# Main_backup1.net
KiCad netlist of a schematic drawn in EAGLE
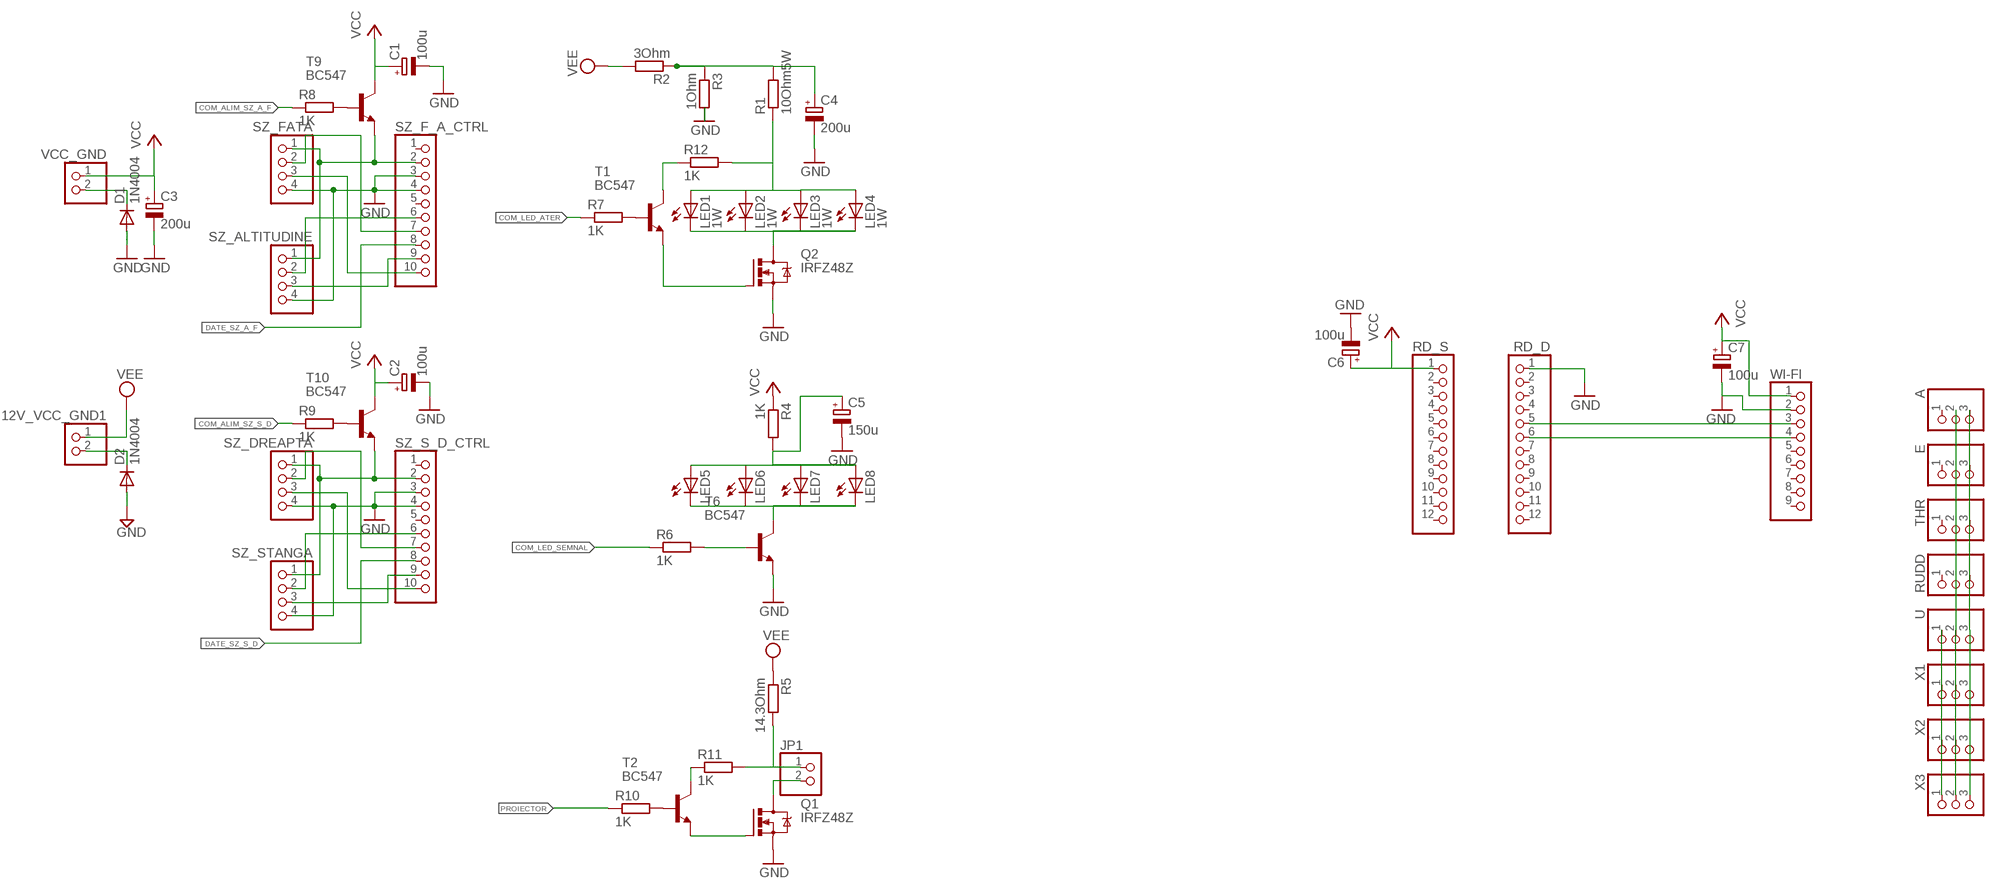
[diagram p0: schematic, sheet 1]

(export (version "E")
  (design (tool "Eeschema 10.0.6"))
  (components
    (comp (ref "12V_VCC_GND1")
      (value "PINHD-1X2")
      (footprint "eagle-import:1X02")
      (libsource (lib "eagle-import") (part "PINHD-1X2"))
    )
    (comp (ref "A")
      (value "PINHD-1X3/90")
      (footprint "eagle-import:1X03_90")
      (libsource (lib "eagle-import") (part "PINHD-1X3/90"))
    )
    (comp (ref "C1")
      (value "100u")
      (footprint "eagle-import:E2-5")
      (libsource (lib "eagle-import") (part "CPOL-EUE2-5"))
    )
    (comp (ref "C2")
      (value "100u")
      (footprint "eagle-import:E2-5")
      (libsource (lib "eagle-import") (part "CPOL-EUE2-5"))
    )
    (comp (ref "C3")
      (value "200u")
      (footprint "eagle-import:E2-5")
      (libsource (lib "eagle-import") (part "CPOL-EUE2-5"))
    )
    (comp (ref "C4")
      (value "200u")
      (footprint "eagle-import:E2-5")
      (libsource (lib "eagle-import") (part "CPOL-EUE2-5"))
    )
    (comp (ref "C5")
      (value "150u")
      (footprint "eagle-import:E2-5")
      (libsource (lib "eagle-import") (part "CPOL-EUE2-5"))
    )
    (comp (ref "C6")
      (value "100u")
      (footprint "eagle-import:E2-5")
      (libsource (lib "eagle-import") (part "CPOL-EUE2-5"))
    )
    (comp (ref "C7")
      (value "100u")
      (footprint "eagle-import:E2-5")
      (libsource (lib "eagle-import") (part "CPOL-EUE2-5"))
    )
    (comp (ref "D1")
      (value "1N4004")
      (footprint "eagle-import:DO41-10")
      (libsource (lib "eagle-import") (part "1N4004"))
    )
    (comp (ref "D2")
      (value "1N4004")
      (footprint "eagle-import:DO41-10")
      (libsource (lib "eagle-import") (part "1N4004"))
    )
    (comp (ref "E")
      (value "PINHD-1X3/90")
      (footprint "eagle-import:1X03_90")
      (libsource (lib "eagle-import") (part "PINHD-1X3/90"))
    )
    (comp (ref "JP1")
      (value "PINHD-1X2")
      (footprint "eagle-import:1X02")
      (libsource (lib "eagle-import") (part "PINHD-1X2"))
    )
    (comp (ref "LED1")
      (value "1W")
      (footprint "eagle-import:OSRAM-SIDELED")
      (libsource (lib "eagle-import") (part "LEDSIDELED"))
    )
    (comp (ref "LED2")
      (value "1W")
      (footprint "eagle-import:OSRAM-SIDELED")
      (libsource (lib "eagle-import") (part "LEDSIDELED"))
    )
    (comp (ref "LED3")
      (value "1W")
      (footprint "eagle-import:OSRAM-SIDELED")
      (libsource (lib "eagle-import") (part "LEDSIDELED"))
    )
    (comp (ref "LED4")
      (value "1W")
      (footprint "eagle-import:OSRAM-SIDELED")
      (libsource (lib "eagle-import") (part "LEDSIDELED"))
    )
    (comp (ref "LED5")
      (value "LED5MM")
      (footprint "eagle-import:LED5MM")
      (libsource (lib "eagle-import") (part "LED5MM"))
    )
    (comp (ref "LED6")
      (value "LED5MM")
      (footprint "eagle-import:LED5MM")
      (libsource (lib "eagle-import") (part "LED5MM"))
    )
    (comp (ref "LED7")
      (value "LED5MM")
      (footprint "eagle-import:LED5MM")
      (libsource (lib "eagle-import") (part "LED5MM"))
    )
    (comp (ref "LED8")
      (value "LED5MM")
      (footprint "eagle-import:LED5MM")
      (libsource (lib "eagle-import") (part "LED5MM"))
    )
    (comp (ref "Q1")
      (value "IRFZ48Z")
      (footprint "eagle-import:TO220BH")
      (libsource (lib "eagle-import") (part "IRFZ48Z"))
    )
    (comp (ref "Q2")
      (value "IRFZ48Z")
      (footprint "eagle-import:TO220BH")
      (libsource (lib "eagle-import") (part "IRFZ48Z"))
    )
    (comp (ref "R1")
      (value "10Ohm5W")
      (footprint "eagle-import:0309_12")
      (libsource (lib "eagle-import") (part "R-EU_0309/12"))
    )
    (comp (ref "R2")
      (value "3Ohm")
      (footprint "eagle-import:0309_12")
      (libsource (lib "eagle-import") (part "R-EU_0309/12"))
    )
    (comp (ref "R3")
      (value "1Ohm")
      (footprint "eagle-import:0309_12")
      (libsource (lib "eagle-import") (part "R-EU_0309/12"))
    )
    (comp (ref "R4")
      (value "1K")
      (footprint "eagle-import:0309_12")
      (libsource (lib "eagle-import") (part "R-EU_0309/12"))
    )
    (comp (ref "R5")
      (value "14.3Ohm")
      (footprint "eagle-import:0309_12")
      (libsource (lib "eagle-import") (part "R-EU_0309/12"))
    )
    (comp (ref "R6")
      (value "1K")
      (footprint "eagle-import:0309_12")
      (libsource (lib "eagle-import") (part "R-EU_0309/12"))
    )
    (comp (ref "R7")
      (value "1K")
      (footprint "eagle-import:0309_12")
      (libsource (lib "eagle-import") (part "R-EU_0309/12"))
    )
    (comp (ref "R8")
      (value "1K")
      (footprint "eagle-import:0309_12")
      (libsource (lib "eagle-import") (part "R-EU_0309/12"))
    )
    (comp (ref "R9")
      (value "1K")
      (footprint "eagle-import:0309_12")
      (libsource (lib "eagle-import") (part "R-EU_0309/12"))
    )
    (comp (ref "R10")
      (value "1K")
      (footprint "eagle-import:0309_12")
      (libsource (lib "eagle-import") (part "R-EU_0309/12"))
    )
    (comp (ref "R11")
      (value "1K")
      (footprint "eagle-import:0309_12")
      (libsource (lib "eagle-import") (part "R-EU_0309/12"))
    )
    (comp (ref "R12")
      (value "1K")
      (footprint "eagle-import:0309_12")
      (libsource (lib "eagle-import") (part "R-EU_0309/12"))
    )
    (comp (ref "RD_D")
      (value "PINHD-1X12")
      (footprint "eagle-import:1X12")
      (libsource (lib "eagle-import") (part "PINHD-1X12"))
    )
    (comp (ref "RD_S")
      (value "PINHD-1X12")
      (footprint "eagle-import:1X12")
      (libsource (lib "eagle-import") (part "PINHD-1X12"))
    )
    (comp (ref "RUDD")
      (value "PINHD-1X3/90")
      (footprint "eagle-import:1X03_90")
      (libsource (lib "eagle-import") (part "PINHD-1X3/90"))
    )
    (comp (ref "SZ_ALTITUDINE")
      (value "PINHD-1X4")
      (footprint "eagle-import:1X04")
      (libsource (lib "eagle-import") (part "PINHD-1X4"))
    )
    (comp (ref "SZ_DREAPTA")
      (value "PINHD-1X4")
      (footprint "eagle-import:1X04")
      (libsource (lib "eagle-import") (part "PINHD-1X4"))
    )
    (comp (ref "SZ_FATA")
      (value "PINHD-1X4")
      (footprint "eagle-import:1X04")
      (libsource (lib "eagle-import") (part "PINHD-1X4"))
    )
    (comp (ref "SZ_F_A_CTRL")
      (value "PINHD-1X10")
      (footprint "eagle-import:1X10")
      (libsource (lib "eagle-import") (part "PINHD-1X10"))
    )
    (comp (ref "SZ_STANGA")
      (value "PINHD-1X4")
      (footprint "eagle-import:1X04")
      (libsource (lib "eagle-import") (part "PINHD-1X4"))
    )
    (comp (ref "SZ_S_D_CTRL")
      (value "PINHD-1X10")
      (footprint "eagle-import:1X10")
      (libsource (lib "eagle-import") (part "PINHD-1X10"))
    )
    (comp (ref "T1")
      (value "BC547")
      (footprint "eagle-import:TO92")
      (libsource (lib "eagle-import") (part "BC547"))
    )
    (comp (ref "T2")
      (value "BC547")
      (footprint "eagle-import:TO92")
      (libsource (lib "eagle-import") (part "BC547"))
    )
    (comp (ref "T6")
      (value "BC547")
      (footprint "eagle-import:TO92")
      (libsource (lib "eagle-import") (part "BC547"))
    )
    (comp (ref "T9")
      (value "BC547")
      (footprint "eagle-import:TO92")
      (libsource (lib "eagle-import") (part "BC547"))
    )
    (comp (ref "T10")
      (value "BC547")
      (footprint "eagle-import:TO92")
      (libsource (lib "eagle-import") (part "BC547"))
    )
    (comp (ref "THR")
      (value "PINHD-1X3/90")
      (footprint "eagle-import:1X03_90")
      (libsource (lib "eagle-import") (part "PINHD-1X3/90"))
    )
    (comp (ref "U")
      (value "PINHD-1X3/90")
      (footprint "eagle-import:1X03_90")
      (libsource (lib "eagle-import") (part "PINHD-1X3/90"))
    )
    (comp (ref "VCC_GND")
      (value "PINHD-1X2")
      (footprint "eagle-import:1X02")
      (libsource (lib "eagle-import") (part "PINHD-1X2"))
    )
    (comp (ref "WI-FI")
      (value "PINHD-1X9")
      (footprint "eagle-import:1X09")
      (libsource (lib "eagle-import") (part "PINHD-1X9"))
    )
    (comp (ref "X1")
      (value "PINHD-1X3/90")
      (footprint "eagle-import:1X03_90")
      (libsource (lib "eagle-import") (part "PINHD-1X3/90"))
    )
    (comp (ref "X2")
      (value "PINHD-1X3/90")
      (footprint "eagle-import:1X03_90")
      (libsource (lib "eagle-import") (part "PINHD-1X3/90"))
    )
    (comp (ref "X3")
      (value "PINHD-1X3/90")
      (footprint "eagle-import:1X03_90")
      (libsource (lib "eagle-import") (part "PINHD-1X3/90"))
    )
  )
  (nets
    (net (code "1") (name "COM_ALIM_SZ_A_F") (class "Default")
      (node (ref "R8") (pin "1") (pinfunction "1_1") (pintype "passive"))
    )
    (net (code "2") (name "COM_ALIM_SZ_S_D") (class "Default")
      (node (ref "R9") (pin "1") (pinfunction "1_1") (pintype "passive"))
    )
    (net (code "3") (name "COM_LED_ATER") (class "Default")
      (node (ref "R7") (pin "1") (pinfunction "1_1") (pintype "passive"))
    )
    (net (code "4") (name "COM_LED_SEMNAL") (class "Default")
      (node (ref "R6") (pin "1") (pinfunction "1_1") (pintype "passive"))
    )
    (net (code "5") (name "DATE_SZ_A_F") (class "Default")
      (node (ref "SZ_F_A_CTRL") (pin "8") (pinfunction "8_8") (pintype "passive"))
    )
    (net (code "6") (name "DATE_SZ_S_D") (class "Default")
      (node (ref "SZ_S_D_CTRL") (pin "8") (pinfunction "8_8") (pintype "passive"))
    )
    (net (code "7") (name "GND") (class "Default")
      (node (ref "C1") (pin "-") (pinfunction "-_-") (pintype "passive"))
      (node (ref "C2") (pin "-") (pinfunction "-_-") (pintype "passive"))
      (node (ref "C3") (pin "-") (pinfunction "-_-") (pintype "passive"))
      (node (ref "C4") (pin "-") (pinfunction "-_-") (pintype "passive"))
      (node (ref "C5") (pin "-") (pinfunction "-_-") (pintype "passive"))
      (node (ref "C6") (pin "-") (pinfunction "-_-") (pintype "passive"))
      (node (ref "C7") (pin "-") (pinfunction "-_-") (pintype "passive"))
      (node (ref "D1") (pin "A") (pinfunction "A_A") (pintype "passive"))
      (node (ref "D2") (pin "A") (pinfunction "A_A") (pintype "passive"))
      (node (ref "Q1") (pin "S") (pinfunction "S_S") (pintype "passive"))
      (node (ref "Q2") (pin "S") (pinfunction "S_S") (pintype "passive"))
      (node (ref "R3") (pin "2") (pinfunction "2_2") (pintype "passive"))
      (node (ref "RD_D") (pin "1") (pinfunction "1_1") (pintype "passive"))
      (node (ref "SZ_ALTITUDINE") (pin "4") (pinfunction "4_4") (pintype "passive"))
      (node (ref "SZ_DREAPTA") (pin "4") (pinfunction "4_4") (pintype "passive"))
      (node (ref "SZ_FATA") (pin "4") (pinfunction "4_4") (pintype "passive"))
      (node (ref "SZ_F_A_CTRL") (pin "3") (pinfunction "3_3") (pintype "passive"))
      (node (ref "SZ_F_A_CTRL") (pin "4") (pinfunction "4_4") (pintype "passive"))
      (node (ref "SZ_STANGA") (pin "4") (pinfunction "4_4") (pintype "passive"))
      (node (ref "SZ_S_D_CTRL") (pin "3") (pinfunction "3_3") (pintype "passive"))
      (node (ref "SZ_S_D_CTRL") (pin "4") (pinfunction "4_4") (pintype "passive"))
      (node (ref "T6") (pin "1") (pinfunction "E_1") (pintype "passive"))
      (node (ref "WI-FI") (pin "2") (pinfunction "2_2") (pintype "passive"))
    )
    (net (code "8") (name "Net-(12V_VCC_GND1-Pad2)") (class "Default")
      (node (ref "12V_VCC_GND1") (pin "2") (pinfunction "2_2") (pintype "passive"))
      (node (ref "D2") (pin "C") (pinfunction "C_C") (pintype "passive"))
    )
    (net (code "9") (name "Net-(A-Pad2)") (class "Default")
      (node (ref "A") (pin "2") (pinfunction "2_2") (pintype "passive"))
      (node (ref "E") (pin "2") (pinfunction "2_2") (pintype "passive"))
      (node (ref "RUDD") (pin "2") (pinfunction "2_2") (pintype "passive"))
      (node (ref "THR") (pin "2") (pinfunction "2_2") (pintype "passive"))
      (node (ref "U") (pin "2") (pinfunction "2_2") (pintype "passive"))
      (node (ref "X1") (pin "2") (pinfunction "2_2") (pintype "passive"))
      (node (ref "X2") (pin "2") (pinfunction "2_2") (pintype "passive"))
      (node (ref "X3") (pin "2") (pinfunction "2_2") (pintype "passive"))
    )
    (net (code "10") (name "Net-(A-Pad3)") (class "Default")
      (node (ref "A") (pin "3") (pinfunction "3_3") (pintype "passive"))
      (node (ref "E") (pin "3") (pinfunction "3_3") (pintype "passive"))
      (node (ref "RUDD") (pin "3") (pinfunction "3_3") (pintype "passive"))
      (node (ref "THR") (pin "3") (pinfunction "3_3") (pintype "passive"))
      (node (ref "U") (pin "3") (pinfunction "3_3") (pintype "passive"))
      (node (ref "X1") (pin "3") (pinfunction "3_3") (pintype "passive"))
      (node (ref "X2") (pin "3") (pinfunction "3_3") (pintype "passive"))
      (node (ref "X3") (pin "3") (pinfunction "3_3") (pintype "passive"))
    )
    (net (code "11") (name "Net-(C4-Pad+)") (class "Default")
      (node (ref "C4") (pin "+") (pinfunction "+_+") (pintype "passive"))
      (node (ref "R1") (pin "2") (pinfunction "2_2") (pintype "passive"))
      (node (ref "R2") (pin "1") (pinfunction "1_1") (pintype "passive"))
      (node (ref "R3") (pin "1") (pinfunction "1_1") (pintype "passive"))
    )
    (net (code "12") (name "Net-(C5-Pad+)") (class "Default")
      (node (ref "C5") (pin "+") (pinfunction "+_+") (pintype "passive"))
      (node (ref "LED5") (pin "A") (pinfunction "A_A") (pintype "passive"))
      (node (ref "LED6") (pin "A") (pinfunction "A_A") (pintype "passive"))
      (node (ref "LED7") (pin "A") (pinfunction "A_A") (pintype "passive"))
      (node (ref "LED8") (pin "A") (pinfunction "A_A") (pintype "passive"))
      (node (ref "R4") (pin "2") (pinfunction "2_2") (pintype "passive"))
    )
    (net (code "13") (name "Net-(D1-PadC)") (class "Default")
      (node (ref "D1") (pin "C") (pinfunction "C_C") (pintype "passive"))
      (node (ref "VCC_GND") (pin "2") (pinfunction "2_2") (pintype "passive"))
    )
    (net (code "14") (name "Net-(JP1-Pad1)") (class "Default")
      (node (ref "JP1") (pin "1") (pinfunction "1_1") (pintype "passive"))
      (node (ref "R11") (pin "2") (pinfunction "2_2") (pintype "passive"))
      (node (ref "R5") (pin "2") (pinfunction "2_2") (pintype "passive"))
    )
    (net (code "15") (name "Net-(JP1-Pad2)") (class "Default")
      (node (ref "JP1") (pin "2") (pinfunction "2_2") (pintype "passive"))
      (node (ref "Q1") (pin "D") (pinfunction "D_D") (pintype "passive"))
    )
    (net (code "16") (name "Net-(LED1-PadA)") (class "Default")
      (node (ref "LED1") (pin "A") (pinfunction "A_A") (pintype "passive"))
      (node (ref "LED2") (pin "A") (pinfunction "A_A") (pintype "passive"))
      (node (ref "LED3") (pin "A") (pinfunction "A_A") (pintype "passive"))
      (node (ref "LED4") (pin "A") (pinfunction "A_A") (pintype "passive"))
      (node (ref "R1") (pin "1") (pinfunction "1_1") (pintype "passive"))
      (node (ref "R12") (pin "2") (pinfunction "2_2") (pintype "passive"))
    )
    (net (code "17") (name "Net-(LED1-PadC)") (class "Default")
      (node (ref "LED1") (pin "C") (pinfunction "C_C") (pintype "passive"))
      (node (ref "LED2") (pin "C") (pinfunction "C_C") (pintype "passive"))
      (node (ref "LED3") (pin "C") (pinfunction "C_C") (pintype "passive"))
      (node (ref "LED4") (pin "C") (pinfunction "C_C") (pintype "passive"))
      (node (ref "Q2") (pin "D") (pinfunction "D_D") (pintype "passive"))
    )
    (net (code "18") (name "Net-(LED5-C)") (class "Default")
      (node (ref "LED5") (pin "K") (pinfunction "C_K") (pintype "passive"))
      (node (ref "LED6") (pin "K") (pinfunction "C_K") (pintype "passive"))
      (node (ref "LED7") (pin "K") (pinfunction "C_K") (pintype "passive"))
      (node (ref "LED8") (pin "K") (pinfunction "C_K") (pintype "passive"))
      (node (ref "T6") (pin "3") (pinfunction "C_3") (pintype "passive"))
    )
    (net (code "19") (name "Net-(RD_D-Pad5)") (class "Default")
      (node (ref "RD_D") (pin "5") (pinfunction "5_5") (pintype "passive"))
      (node (ref "WI-FI") (pin "3") (pinfunction "3_3") (pintype "passive"))
    )
    (net (code "20") (name "Net-(RD_D-Pad6)") (class "Default")
      (node (ref "RD_D") (pin "6") (pinfunction "6_6") (pintype "passive"))
      (node (ref "WI-FI") (pin "4") (pinfunction "4_4") (pintype "passive"))
    )
    (net (code "21") (name "Net-(SZ_ALTITUDINE-Pad2)") (class "Default")
      (node (ref "SZ_ALTITUDINE") (pin "2") (pinfunction "2_2") (pintype "passive"))
      (node (ref "SZ_F_A_CTRL") (pin "6") (pinfunction "6_6") (pintype "passive"))
    )
    (net (code "22") (name "Net-(SZ_ALTITUDINE-Pad3)") (class "Default")
      (node (ref "SZ_ALTITUDINE") (pin "3") (pinfunction "3_3") (pintype "passive"))
      (node (ref "SZ_F_A_CTRL") (pin "9") (pinfunction "9_9") (pintype "passive"))
    )
    (net (code "23") (name "Net-(SZ_DREAPTA-Pad2)") (class "Default")
      (node (ref "SZ_DREAPTA") (pin "2") (pinfunction "2_2") (pintype "passive"))
      (node (ref "SZ_S_D_CTRL") (pin "7") (pinfunction "7_7") (pintype "passive"))
    )
    (net (code "24") (name "Net-(SZ_DREAPTA-Pad3)") (class "Default")
      (node (ref "SZ_DREAPTA") (pin "3") (pinfunction "3_3") (pintype "passive"))
      (node (ref "SZ_S_D_CTRL") (pin "10") (pinfunction "10_10") (pintype "passive"))
    )
    (net (code "25") (name "Net-(SZ_FATA-Pad2)") (class "Default")
      (node (ref "SZ_FATA") (pin "2") (pinfunction "2_2") (pintype "passive"))
      (node (ref "SZ_F_A_CTRL") (pin "7") (pinfunction "7_7") (pintype "passive"))
    )
    (net (code "26") (name "Net-(SZ_FATA-Pad3)") (class "Default")
      (node (ref "SZ_FATA") (pin "3") (pinfunction "3_3") (pintype "passive"))
      (node (ref "SZ_F_A_CTRL") (pin "10") (pinfunction "10_10") (pintype "passive"))
    )
    (net (code "27") (name "Net-(SZ_STANGA-Pad2)") (class "Default")
      (node (ref "SZ_STANGA") (pin "2") (pinfunction "2_2") (pintype "passive"))
      (node (ref "SZ_S_D_CTRL") (pin "6") (pinfunction "6_6") (pintype "passive"))
    )
    (net (code "28") (name "Net-(SZ_STANGA-Pad3)") (class "Default")
      (node (ref "SZ_STANGA") (pin "3") (pinfunction "3_3") (pintype "passive"))
      (node (ref "SZ_S_D_CTRL") (pin "9") (pinfunction "9_9") (pintype "passive"))
    )
    (net (code "29") (name "Net-(T1-B)") (class "Default")
      (node (ref "R7") (pin "2") (pinfunction "2_2") (pintype "passive"))
      (node (ref "T1") (pin "2") (pinfunction "B_2") (pintype "passive"))
    )
    (net (code "30") (name "Net-(T1-C)") (class "Default")
      (node (ref "R12") (pin "1") (pinfunction "1_1") (pintype "passive"))
      (node (ref "T1") (pin "3") (pinfunction "C_3") (pintype "passive"))
    )
    (net (code "31") (name "Net-(T1-E)") (class "Default")
      (node (ref "Q2") (pin "G") (pinfunction "G_G") (pintype "passive"))
      (node (ref "T1") (pin "1") (pinfunction "E_1") (pintype "passive"))
    )
    (net (code "32") (name "Net-(T2-B)") (class "Default")
      (node (ref "R10") (pin "2") (pinfunction "2_2") (pintype "passive"))
      (node (ref "T2") (pin "2") (pinfunction "B_2") (pintype "passive"))
    )
    (net (code "33") (name "Net-(T2-C)") (class "Default")
      (node (ref "R11") (pin "1") (pinfunction "1_1") (pintype "passive"))
      (node (ref "T2") (pin "3") (pinfunction "C_3") (pintype "passive"))
    )
    (net (code "34") (name "Net-(T2-E)") (class "Default")
      (node (ref "Q1") (pin "G") (pinfunction "G_G") (pintype "passive"))
      (node (ref "T2") (pin "1") (pinfunction "E_1") (pintype "passive"))
    )
    (net (code "35") (name "Net-(T6-B)") (class "Default")
      (node (ref "R6") (pin "2") (pinfunction "2_2") (pintype "passive"))
      (node (ref "T6") (pin "2") (pinfunction "B_2") (pintype "passive"))
    )
    (net (code "36") (name "Net-(T9-B)") (class "Default")
      (node (ref "R8") (pin "2") (pinfunction "2_2") (pintype "passive"))
      (node (ref "T9") (pin "2") (pinfunction "B_2") (pintype "passive"))
    )
    (net (code "37") (name "Net-(T9-E)") (class "Default")
      (node (ref "SZ_ALTITUDINE") (pin "1") (pinfunction "1_1") (pintype "passive"))
      (node (ref "SZ_FATA") (pin "1") (pinfunction "1_1") (pintype "passive"))
      (node (ref "SZ_F_A_CTRL") (pin "2") (pinfunction "2_2") (pintype "passive"))
      (node (ref "T9") (pin "1") (pinfunction "E_1") (pintype "passive"))
    )
    (net (code "38") (name "Net-(T10-B)") (class "Default")
      (node (ref "R9") (pin "2") (pinfunction "2_2") (pintype "passive"))
      (node (ref "T10") (pin "2") (pinfunction "B_2") (pintype "passive"))
    )
    (net (code "39") (name "Net-(T10-E)") (class "Default")
      (node (ref "SZ_DREAPTA") (pin "1") (pinfunction "1_1") (pintype "passive"))
      (node (ref "SZ_STANGA") (pin "1") (pinfunction "1_1") (pintype "passive"))
      (node (ref "SZ_S_D_CTRL") (pin "2") (pinfunction "2_2") (pintype "passive"))
      (node (ref "T10") (pin "1") (pinfunction "E_1") (pintype "passive"))
    )
    (net (code "40") (name "Net-(U-Pad1)") (class "Default")
      (node (ref "U") (pin "1") (pinfunction "1_1") (pintype "passive"))
      (node (ref "X1") (pin "1") (pinfunction "1_1") (pintype "passive"))
      (node (ref "X2") (pin "1") (pinfunction "1_1") (pintype "passive"))
      (node (ref "X3") (pin "1") (pinfunction "1_1") (pintype "passive"))
    )
    (net (code "41") (name "PROIECTOR") (class "Default")
      (node (ref "R10") (pin "1") (pinfunction "1_1") (pintype "passive"))
    )
    (net (code "42") (name "VCC") (class "Default")
      (node (ref "C1") (pin "+") (pinfunction "+_+") (pintype "passive"))
      (node (ref "C2") (pin "+") (pinfunction "+_+") (pintype "passive"))
      (node (ref "C3") (pin "+") (pinfunction "+_+") (pintype "passive"))
      (node (ref "C6") (pin "+") (pinfunction "+_+") (pintype "passive"))
      (node (ref "C7") (pin "+") (pinfunction "+_+") (pintype "passive"))
      (node (ref "R4") (pin "1") (pinfunction "1_1") (pintype "passive"))
      (node (ref "RD_S") (pin "1") (pinfunction "1_1") (pintype "passive"))
      (node (ref "T10") (pin "3") (pinfunction "C_3") (pintype "passive"))
      (node (ref "T9") (pin "3") (pinfunction "C_3") (pintype "passive"))
      (node (ref "VCC_GND") (pin "1") (pinfunction "1_1") (pintype "passive"))
      (node (ref "WI-FI") (pin "1") (pinfunction "1_1") (pintype "passive"))
    )
    (net (code "43") (name "VEE") (class "Default")
      (node (ref "12V_VCC_GND1") (pin "1") (pinfunction "1_1") (pintype "passive"))
      (node (ref "R2") (pin "2") (pinfunction "2_2") (pintype "passive"))
      (node (ref "R5") (pin "1") (pinfunction "1_1") (pintype "passive"))
    )
    (net (code "44") (name "unconnected-(A-Pad1)") (class "Default")
      (node (ref "A") (pin "1") (pinfunction "1_1") (pintype "passive"))
    )
    (net (code "45") (name "unconnected-(E-Pad1)") (class "Default")
      (node (ref "E") (pin "1") (pinfunction "1_1") (pintype "passive"))
    )
    (net (code "46") (name "unconnected-(RD_D-Pad2)") (class "Default")
      (node (ref "RD_D") (pin "2") (pinfunction "2_2") (pintype "passive"))
    )
    (net (code "47") (name "unconnected-(RD_D-Pad3)") (class "Default")
      (node (ref "RD_D") (pin "3") (pinfunction "3_3") (pintype "passive"))
    )
    (net (code "48") (name "unconnected-(RD_D-Pad4)") (class "Default")
      (node (ref "RD_D") (pin "4") (pinfunction "4_4") (pintype "passive"))
    )
    (net (code "49") (name "unconnected-(RD_D-Pad7)") (class "Default")
      (node (ref "RD_D") (pin "7") (pinfunction "7_7") (pintype "passive"))
    )
    (net (code "50") (name "unconnected-(RD_D-Pad8)") (class "Default")
      (node (ref "RD_D") (pin "8") (pinfunction "8_8") (pintype "passive"))
    )
    (net (code "51") (name "unconnected-(RD_D-Pad9)") (class "Default")
      (node (ref "RD_D") (pin "9") (pinfunction "9_9") (pintype "passive"))
    )
    (net (code "52") (name "unconnected-(RD_D-Pad10)") (class "Default")
      (node (ref "RD_D") (pin "10") (pinfunction "10_10") (pintype "passive"))
    )
    (net (code "53") (name "unconnected-(RD_D-Pad11)") (class "Default")
      (node (ref "RD_D") (pin "11") (pinfunction "11_11") (pintype "passive"))
    )
    (net (code "54") (name "unconnected-(RD_D-Pad12)") (class "Default")
      (node (ref "RD_D") (pin "12") (pinfunction "12_12") (pintype "passive"))
    )
    (net (code "55") (name "unconnected-(RD_S-Pad2)") (class "Default")
      (node (ref "RD_S") (pin "2") (pinfunction "2_2") (pintype "passive"))
    )
    (net (code "56") (name "unconnected-(RD_S-Pad3)") (class "Default")
      (node (ref "RD_S") (pin "3") (pinfunction "3_3") (pintype "passive"))
    )
    (net (code "57") (name "unconnected-(RD_S-Pad4)") (class "Default")
      (node (ref "RD_S") (pin "4") (pinfunction "4_4") (pintype "passive"))
    )
    (net (code "58") (name "unconnected-(RD_S-Pad5)") (class "Default")
      (node (ref "RD_S") (pin "5") (pinfunction "5_5") (pintype "passive"))
    )
    (net (code "59") (name "unconnected-(RD_S-Pad6)") (class "Default")
      (node (ref "RD_S") (pin "6") (pinfunction "6_6") (pintype "passive"))
    )
    (net (code "60") (name "unconnected-(RD_S-Pad7)") (class "Default")
      (node (ref "RD_S") (pin "7") (pinfunction "7_7") (pintype "passive"))
    )
    (net (code "61") (name "unconnected-(RD_S-Pad8)") (class "Default")
      (node (ref "RD_S") (pin "8") (pinfunction "8_8") (pintype "passive"))
    )
    (net (code "62") (name "unconnected-(RD_S-Pad9)") (class "Default")
      (node (ref "RD_S") (pin "9") (pinfunction "9_9") (pintype "passive"))
    )
    (net (code "63") (name "unconnected-(RD_S-Pad10)") (class "Default")
      (node (ref "RD_S") (pin "10") (pinfunction "10_10") (pintype "passive"))
    )
    (net (code "64") (name "unconnected-(RD_S-Pad11)") (class "Default")
      (node (ref "RD_S") (pin "11") (pinfunction "11_11") (pintype "passive"))
    )
    (net (code "65") (name "unconnected-(RD_S-Pad12)") (class "Default")
      (node (ref "RD_S") (pin "12") (pinfunction "12_12") (pintype "passive"))
    )
    (net (code "66") (name "unconnected-(RUDD-Pad1)") (class "Default")
      (node (ref "RUDD") (pin "1") (pinfunction "1_1") (pintype "passive"))
    )
    (net (code "67") (name "unconnected-(SZ_F_A_CTRL-Pad1)") (class "Default")
      (node (ref "SZ_F_A_CTRL") (pin "1") (pinfunction "1_1") (pintype "passive"))
    )
    (net (code "68") (name "unconnected-(SZ_F_A_CTRL-Pad5)") (class "Default")
      (node (ref "SZ_F_A_CTRL") (pin "5") (pinfunction "5_5") (pintype "passive"))
    )
    (net (code "69") (name "unconnected-(SZ_S_D_CTRL-Pad1)") (class "Default")
      (node (ref "SZ_S_D_CTRL") (pin "1") (pinfunction "1_1") (pintype "passive"))
    )
    (net (code "70") (name "unconnected-(SZ_S_D_CTRL-Pad5)") (class "Default")
      (node (ref "SZ_S_D_CTRL") (pin "5") (pinfunction "5_5") (pintype "passive"))
    )
    (net (code "71") (name "unconnected-(THR-Pad1)") (class "Default")
      (node (ref "THR") (pin "1") (pinfunction "1_1") (pintype "passive"))
    )
    (net (code "72") (name "unconnected-(WI-FI-Pad5)") (class "Default")
      (node (ref "WI-FI") (pin "5") (pinfunction "5_5") (pintype "passive"))
    )
    (net (code "73") (name "unconnected-(WI-FI-Pad6)") (class "Default")
      (node (ref "WI-FI") (pin "6") (pinfunction "6_6") (pintype "passive"))
    )
    (net (code "74") (name "unconnected-(WI-FI-Pad7)") (class "Default")
      (node (ref "WI-FI") (pin "7") (pinfunction "7_7") (pintype "passive"))
    )
    (net (code "75") (name "unconnected-(WI-FI-Pad8)") (class "Default")
      (node (ref "WI-FI") (pin "8") (pinfunction "8_8") (pintype "passive"))
    )
    (net (code "76") (name "unconnected-(WI-FI-Pad9)") (class "Default")
      (node (ref "WI-FI") (pin "9") (pinfunction "9_9") (pintype "passive"))
    )
  )
)
